# User_Interface.net
KiCad netlist of a schematic drawn in Altium Designer
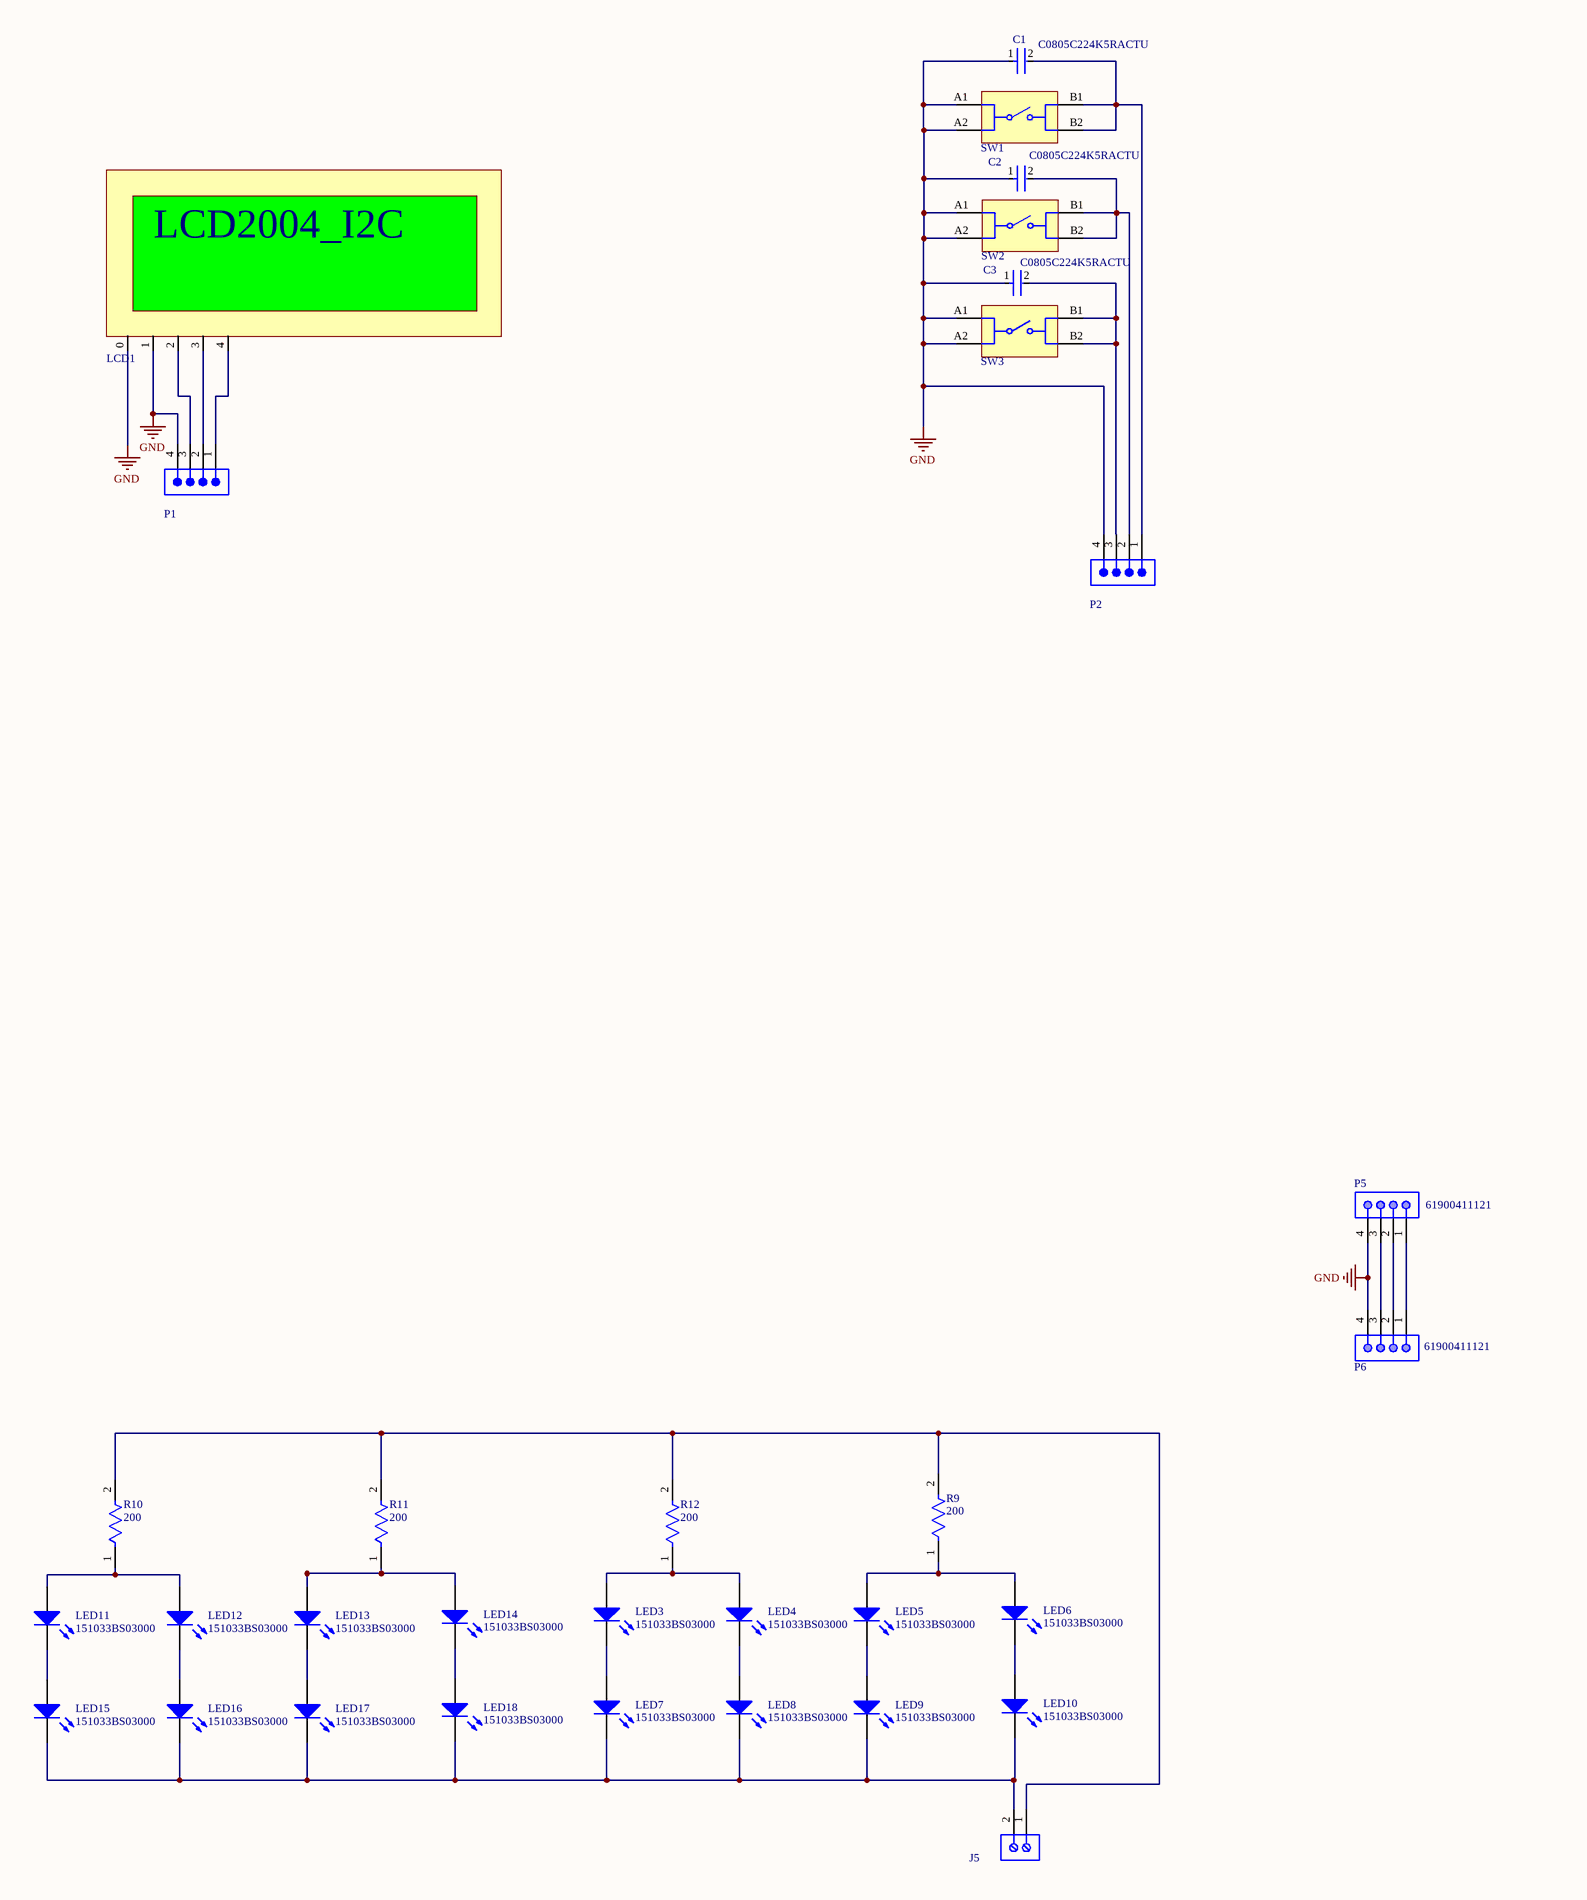
[diagram p0: User_Interface.SchDoc, left]
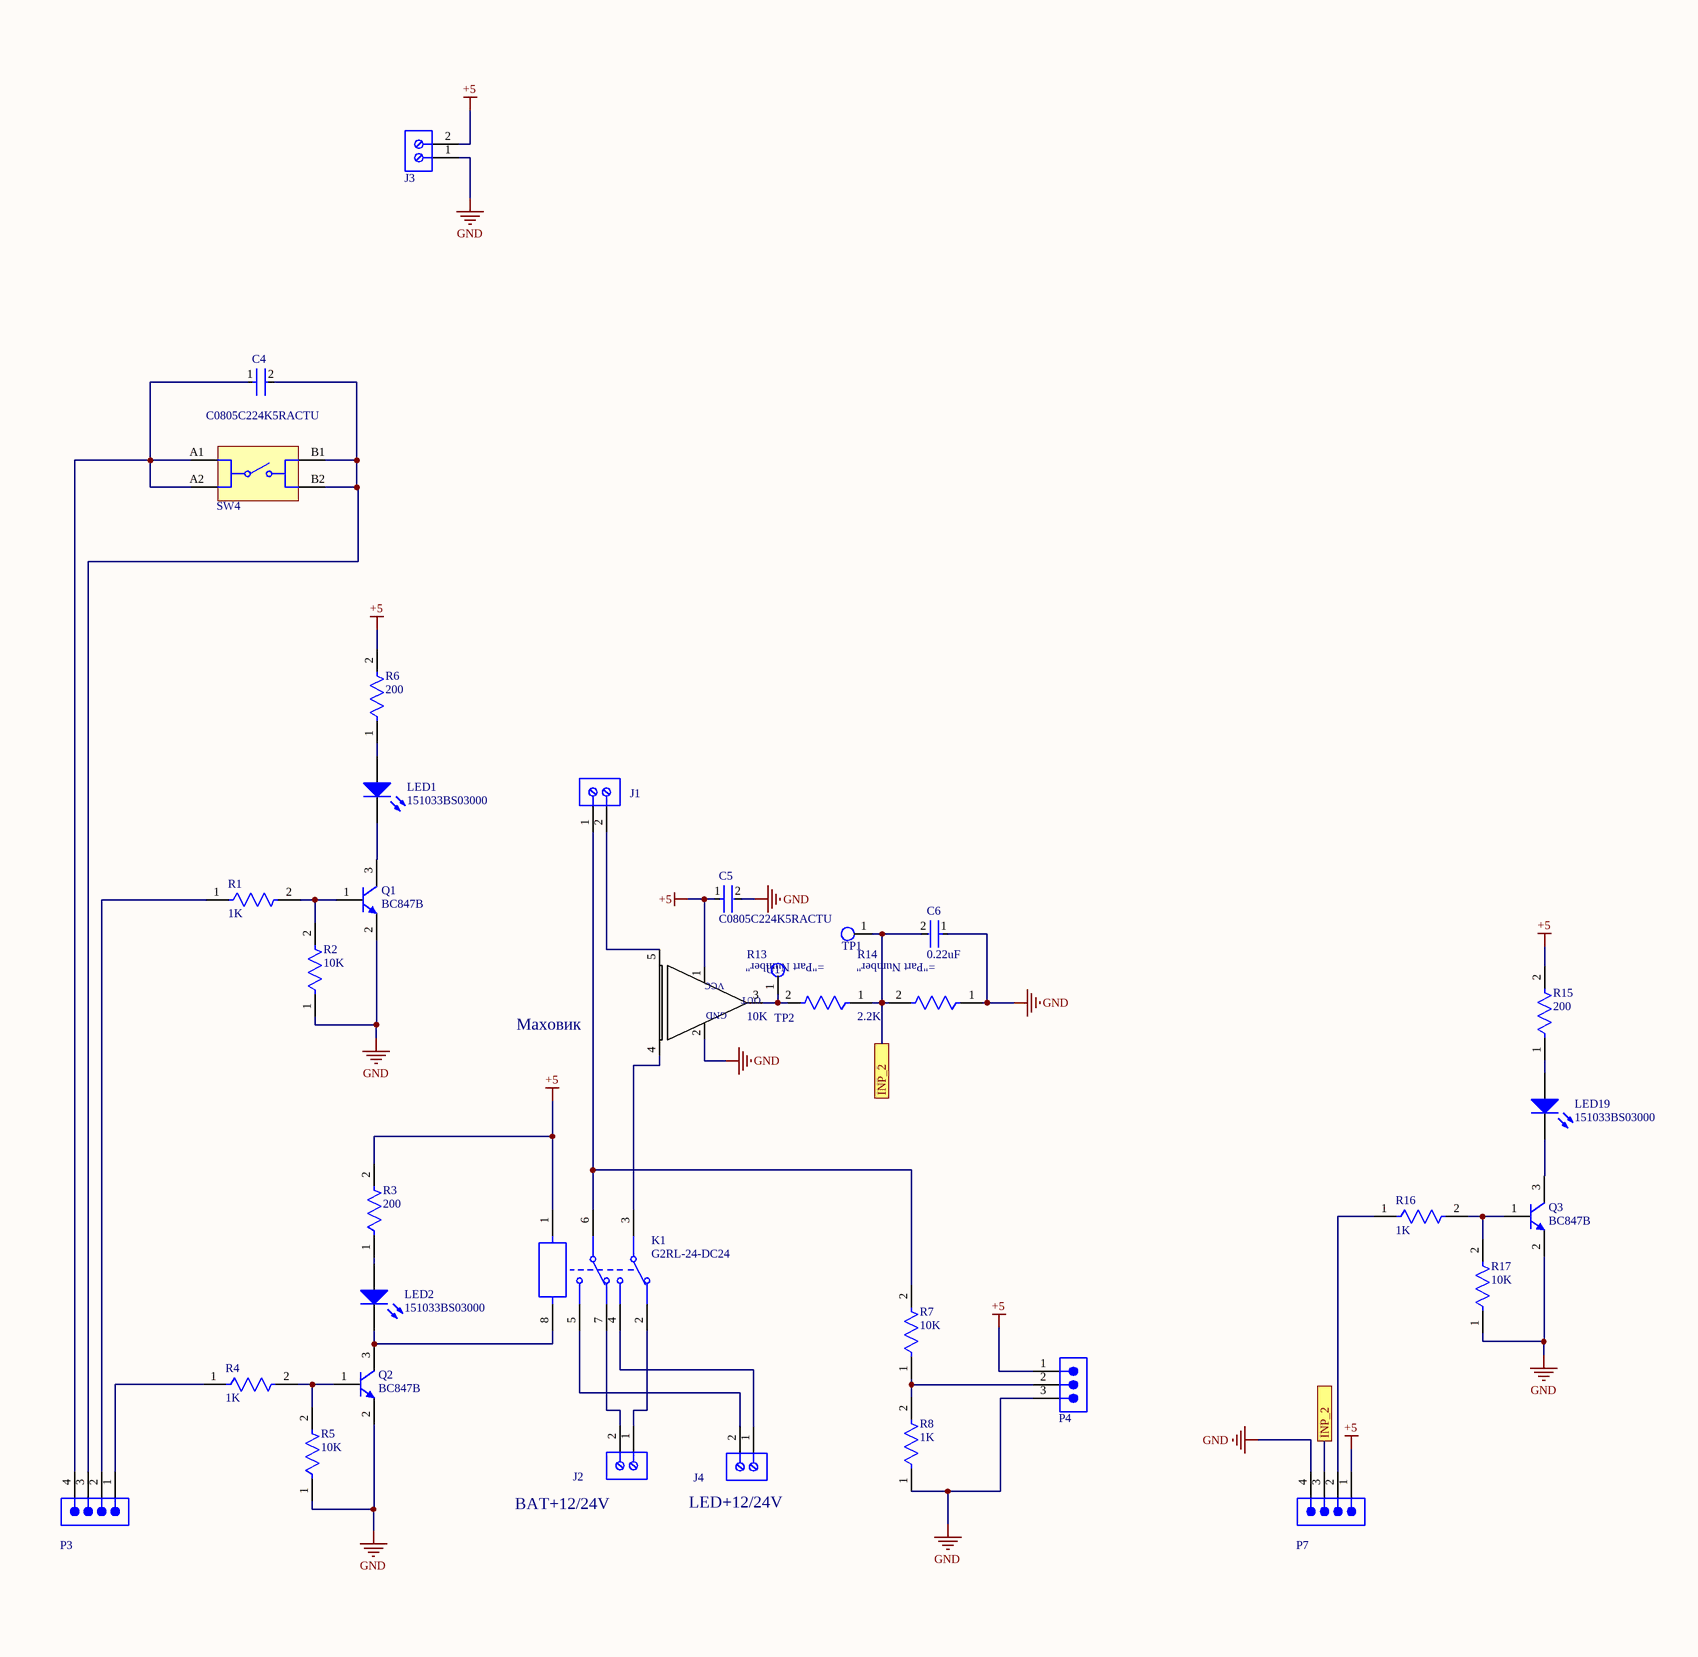
[diagram p1: User_Interface.SchDoc, right]

(export (version "E")
  (design (tool "Eeschema 10.0.6"))
  (components
    (comp (ref "C1")
      (value "C0805C224K5RACTU")
      (footprint "FP-C0805C-DN-IPC_A")
      (description "CAP CER 0.22UF 50V X7R 0805")
      (fields
        (field (name "MANUFACTURER") "KEMET")
        (field (name "OCTOPART") "https://octopart.com/c0805c224k5ractu-kemet-144670")
      )
      (libsource (lib "Pasive_components") (part "CMP-1036-04552-2"))
    )
    (comp (ref "C2")
      (value "C0805C224K5RACTU")
      (footprint "FP-C0805C-DN-IPC_A")
      (description "CAP CER 0.22UF 50V X7R 0805")
      (fields
        (field (name "MANUFACTURER") "KEMET")
        (field (name "OCTOPART") "https://octopart.com/c0805c224k5ractu-kemet-144670")
      )
      (libsource (lib "Pasive_components") (part "CMP-1036-04552-2"))
    )
    (comp (ref "C3")
      (value "C0805C224K5RACTU")
      (footprint "FP-C0805C-DN-IPC_A")
      (description "CAP CER 0.22UF 50V X7R 0805")
      (fields
        (field (name "MANUFACTURER") "KEMET")
        (field (name "OCTOPART") "https://octopart.com/c0805c224k5ractu-kemet-144670")
      )
      (libsource (lib "Pasive_components") (part "CMP-1036-04552-2"))
    )
    (comp (ref "C4")
      (value "C0805C224K5RACTU")
      (footprint "FP-C0805C-DN-IPC_A")
      (description "CAP CER 0.22UF 50V X7R 0805")
      (fields
        (field (name "MANUFACTURER") "KEMET")
        (field (name "OCTOPART") "https://octopart.com/c0805c224k5ractu-kemet-144670")
      )
      (libsource (lib "Pasive_components") (part "CMP-1036-04552-2"))
    )
    (comp (ref "C5")
      (value "C0805C224K5RACTU")
      (footprint "FP-C0805C-DN-MFG")
      (description "CAP CER 0.22UF 50V X7R 0805")
      (fields
        (field (name "MANUFACTURER") "KEMET")
        (field (name "OCTOPART") "https://octopart.com/c0805c224k5ractu-kemet-144670")
      )
      (libsource (lib "Altium Content Vault") (part "b4654b650e69147ec39a6b967a45e02"))
    )
    (comp (ref "C6")
      (value "0.22uF")
      (footprint "FP-C0805C-DN-MFG")
      (description "CAP CER 0.22UF 50V X7R 0805")
      (fields
        (field (name "MANUFACTURER") "KEMET")
        (field (name "OCTOPART") "https://octopart.com/c0805c224k5ractu-kemet-144670")
      )
      (libsource (lib "Altium Content Vault") (part "b4654b650e69147ec39a6b967a45e02"))
    )
    (comp (ref "J1")
      (value "691101710002")
      (footprint "691101710002")
      (description "WR-TBL Series 101 Horizontal Entry Modular, THT, pitch 5mm, 2p")
      (fields (field (name "MANUFACTURER") "Wurth Elektronik"))
      (libsource (lib "Altium_WR-TBL (rev23a)") (part "691101710002"))
    )
    (comp (ref "J2")
      (value "691101710002")
      (footprint "691101710002")
      (description "WR-TBL Series 101 Horizontal Entry Modular, THT, pitch 5mm, 2p")
      (fields (field (name "MANUFACTURER") "Wurth Elektronik"))
      (libsource (lib "Altium_WR-TBL (rev23a)") (part "691101710002"))
    )
    (comp (ref "J3")
      (value "691101710002")
      (footprint "691101710002")
      (description "WR-TBL Series 101 Horizontal Entry Modular, THT, pitch 5mm, 2p")
      (fields (field (name "MANUFACTURER") "Wurth Elektronik"))
      (libsource (lib "Altium_WR-TBL (rev23a)") (part "691101710002"))
    )
    (comp (ref "J4")
      (value "691101710002")
      (footprint "691101710002")
      (description "WR-TBL Series 101 Horizontal Entry Modular, THT, pitch 5mm, 2p")
      (fields (field (name "MANUFACTURER") "Wurth Elektronik"))
      (libsource (lib "Altium_WR-TBL (rev23a)") (part "691101710002"))
    )
    (comp (ref "J5")
      (value "691101710002")
      (footprint "691101710002")
      (description "WR-TBL Series 101 Horizontal Entry Modular, THT, pitch 5mm, 2p")
      (fields (field (name "MANUFACTURER") "Wurth Elektronik"))
      (libsource (lib "Altium_WR-TBL (rev23a)") (part "691101710002"))
    )
    (comp (ref "K1")
      (value "G2RL-24-DC24")
      (footprint "OMRON-G2RL-24_V")
      (fields (field (name "MANUFACTURER") "Omron"))
      (libsource (lib "Altium Content Vault") (part "RELAY-DPDT-8_C"))
    )
    (comp (ref "LCD1")
      (value "2004_I2C")
      (footprint "LCD2004_I2C")
      (libsource (lib "LCD2004_I2C") (part "LCD2004_I2C"))
    )
    (comp (ref "LED1")
      (value "151033BS03000")
      (footprint "Type 3mm")
      (description "THT LED round mono-color waterclear, WL-TMRW , Blue")
      (fields (field (name "MANUFACTURER") "Wuerth Elektronik"))
      (libsource (lib "Optic-LED") (part "151033BS03000"))
    )
    (comp (ref "LED2")
      (value "151033BS03000")
      (footprint "Type 3mm")
      (description "THT LED round mono-color waterclear, WL-TMRW , Blue")
      (fields (field (name "MANUFACTURER") "Wuerth Elektronik"))
      (libsource (lib "Optic-LED") (part "151033BS03000"))
    )
    (comp (ref "LED3")
      (value "151033BS03000")
      (footprint "Type 3mm")
      (description "THT LED round mono-color waterclear, WL-TMRW , Blue")
      (fields (field (name "MANUFACTURER") "Wuerth Elektronik"))
      (libsource (lib "Optic-LED") (part "151033BS03000"))
    )
    (comp (ref "LED4")
      (value "151033BS03000")
      (footprint "Type 3mm")
      (description "THT LED round mono-color waterclear, WL-TMRW , Blue")
      (fields (field (name "MANUFACTURER") "Wuerth Elektronik"))
      (libsource (lib "Optic-LED") (part "151033BS03000"))
    )
    (comp (ref "LED5")
      (value "151033BS03000")
      (footprint "Type 3mm")
      (description "THT LED round mono-color waterclear, WL-TMRW , Blue")
      (fields (field (name "MANUFACTURER") "Wuerth Elektronik"))
      (libsource (lib "Optic-LED") (part "151033BS03000"))
    )
    (comp (ref "LED6")
      (value "151033BS03000")
      (footprint "Type 3mm")
      (description "THT LED round mono-color waterclear, WL-TMRW , Blue")
      (fields (field (name "MANUFACTURER") "Wuerth Elektronik"))
      (libsource (lib "Optic-LED") (part "151033BS03000"))
    )
    (comp (ref "LED7")
      (value "151033BS03000")
      (footprint "Type 3mm")
      (description "THT LED round mono-color waterclear, WL-TMRW , Blue")
      (fields (field (name "MANUFACTURER") "Wuerth Elektronik"))
      (libsource (lib "Optic-LED") (part "151033BS03000"))
    )
    (comp (ref "LED8")
      (value "151033BS03000")
      (footprint "Type 3mm")
      (description "THT LED round mono-color waterclear, WL-TMRW , Blue")
      (fields (field (name "MANUFACTURER") "Wuerth Elektronik"))
      (libsource (lib "Optic-LED") (part "151033BS03000"))
    )
    (comp (ref "LED9")
      (value "151033BS03000")
      (footprint "Type 3mm")
      (description "THT LED round mono-color waterclear, WL-TMRW , Blue")
      (fields (field (name "MANUFACTURER") "Wuerth Elektronik"))
      (libsource (lib "Optic-LED") (part "151033BS03000"))
    )
    (comp (ref "LED10")
      (value "151033BS03000")
      (footprint "Type 3mm")
      (description "THT LED round mono-color waterclear, WL-TMRW , Blue")
      (fields (field (name "MANUFACTURER") "Wuerth Elektronik"))
      (libsource (lib "Optic-LED") (part "151033BS03000"))
    )
    (comp (ref "LED11")
      (value "151033BS03000")
      (footprint "Type 3mm")
      (description "THT LED round mono-color waterclear, WL-TMRW , Blue")
      (fields (field (name "MANUFACTURER") "Wuerth Elektronik"))
      (libsource (lib "Optic-LED") (part "151033BS03000"))
    )
    (comp (ref "LED12")
      (value "151033BS03000")
      (footprint "Type 3mm")
      (description "THT LED round mono-color waterclear, WL-TMRW , Blue")
      (fields (field (name "MANUFACTURER") "Wuerth Elektronik"))
      (libsource (lib "Optic-LED") (part "151033BS03000"))
    )
    (comp (ref "LED13")
      (value "151033BS03000")
      (footprint "Type 3mm")
      (description "THT LED round mono-color waterclear, WL-TMRW , Blue")
      (fields (field (name "MANUFACTURER") "Wuerth Elektronik"))
      (libsource (lib "Optic-LED") (part "151033BS03000"))
    )
    (comp (ref "LED14")
      (value "151033BS03000")
      (footprint "Type 3mm")
      (description "THT LED round mono-color waterclear, WL-TMRW , Blue")
      (fields (field (name "MANUFACTURER") "Wuerth Elektronik"))
      (libsource (lib "Optic-LED") (part "151033BS03000"))
    )
    (comp (ref "LED15")
      (value "151033BS03000")
      (footprint "Type 3mm")
      (description "THT LED round mono-color waterclear, WL-TMRW , Blue")
      (fields (field (name "MANUFACTURER") "Wuerth Elektronik"))
      (libsource (lib "Optic-LED") (part "151033BS03000"))
    )
    (comp (ref "LED16")
      (value "151033BS03000")
      (footprint "Type 3mm")
      (description "THT LED round mono-color waterclear, WL-TMRW , Blue")
      (fields (field (name "MANUFACTURER") "Wuerth Elektronik"))
      (libsource (lib "Optic-LED") (part "151033BS03000"))
    )
    (comp (ref "LED17")
      (value "151033BS03000")
      (footprint "Type 3mm")
      (description "THT LED round mono-color waterclear, WL-TMRW , Blue")
      (fields (field (name "MANUFACTURER") "Wuerth Elektronik"))
      (libsource (lib "Optic-LED") (part "151033BS03000"))
    )
    (comp (ref "LED18")
      (value "151033BS03000")
      (footprint "Type 3mm")
      (description "THT LED round mono-color waterclear, WL-TMRW , Blue")
      (fields (field (name "MANUFACTURER") "Wuerth Elektronik"))
      (libsource (lib "Optic-LED") (part "151033BS03000"))
    )
    (comp (ref "LED19")
      (value "151033BS03000")
      (footprint "Type 3mm")
      (description "THT LED round mono-color waterclear, WL-TMRW , Blue")
      (fields (field (name "MANUFACTURER") "Wuerth Elektronik"))
      (libsource (lib "Optic-LED") (part "151033BS03000"))
    )
    (comp (ref "P1")
      (value "61900411121")
      (footprint "61900411121")
      (description "WR-WTB THT Male Vertical Locking Header, pitch 2.54mm, 4pins")
      (fields (field (name "MANUFACTURER") "Wurth Elektronik"))
      (libsource (lib "Altium_WR-WTB (rev22b)") (part "61900411121"))
    )
    (comp (ref "P2")
      (value "61900411121")
      (footprint "61900411121")
      (description "WR-WTB THT Male Vertical Locking Header, pitch 2.54mm, 4pins")
      (fields (field (name "MANUFACTURER") "Wurth Elektronik"))
      (libsource (lib "Altium_WR-WTB (rev22b)") (part "61900411121"))
    )
    (comp (ref "P3")
      (value "61900411121")
      (footprint "61900411121")
      (description "WR-WTB THT Male Vertical Locking Header, pitch 2.54mm, 4pins")
      (fields (field (name "MANUFACTURER") "Wurth Elektronik"))
      (libsource (lib "Altium_WR-WTB (rev22b)") (part "61900411121"))
    )
    (comp (ref "P4")
      (value "61900311121")
      (footprint "61900311121")
      (description "WR-WTB THT Male Vertical Locking Header, pitch 2.54mm, 3pins")
      (fields (field (name "MANUFACTURER") "Wurth Elektronik"))
      (libsource (lib "Altium_WR-WTB (rev22b)") (part "61900311121"))
    )
    (comp (ref "P5")
      (value "61900411121")
      (footprint "61900411121")
      (description "WR-WTB THT Male Vertical Locking Header, pitch 2.54mm, 4p")
      (fields (field (name "PUBLISHER") "Wurth Elektronik"))
      (libsource (lib "Altium_WR-WTB (rev20a)") (part "61900411121"))
    )
    (comp (ref "P6")
      (value "61900411121")
      (footprint "61900411121")
      (description "WR-WTB THT Male Vertical Locking Header, pitch 2.54mm, 4p")
      (fields (field (name "PUBLISHER") "Wurth Elektronik"))
      (libsource (lib "Altium_WR-WTB (rev20a)") (part "61900411121"))
    )
    (comp (ref "P7")
      (value "61900411121")
      (footprint "61900411121")
      (description "WR-WTB THT Male Vertical Locking Header, pitch 2.54mm, 4pins")
      (fields (field (name "MANUFACTURER") "Wurth Elektronik"))
      (libsource (lib "Altium_WR-WTB (rev22b)") (part "61900411121"))
    )
    (comp (ref "Q1")
      (value "BC847B")
      (footprint "INF-SOT23_M")
      (description "NPN Silicon AF Transistor, 45 V VCEO, 100 mA IC, SOT23, Reel, Green")
      (fields (field (name "MANUFACTURER") "Infineon"))
      (libsource (lib "Altium Content Vault") (part "INF-BJTNPN-BEC-3"))
    )
    (comp (ref "Q2")
      (value "BC847B")
      (footprint "INF-SOT23_M")
      (description "NPN Silicon AF Transistor, 45 V VCEO, 100 mA IC, SOT23, Reel, Green")
      (fields (field (name "MANUFACTURER") "Infineon"))
      (libsource (lib "Altium Content Vault") (part "INF-BJTNPN-BEC-3"))
    )
    (comp (ref "Q3")
      (value "BC847B")
      (footprint "INF-SOT23_M")
      (description "NPN Silicon AF Transistor, 45 V VCEO, 100 mA IC, SOT23, Reel, Green")
      (fields (field (name "MANUFACTURER") "Infineon"))
      (libsource (lib "Altium Content Vault") (part "INF-BJTNPN-BEC-3"))
    )
    (comp (ref "R1")
      (value "1K")
      (footprint "FP-CRCW0805-e3-MFG")
      (description "RES Thick Film, 10kΩ, 1%, 0.125W, 100ppm/°C, 0805")
      (fields (field (name "TOLERANCE") "1%"))
      (libsource (lib "Pasive_components") (part "CMP-2001-04908-2"))
    )
    (comp (ref "R2")
      (value "10K")
      (footprint "FP-CRCW0805-e3-MFG")
      (description "RES Thick Film, 10kΩ, 1%, 0.125W, 100ppm/°C, 0805")
      (fields (field (name "TOLERANCE") "1%"))
      (libsource (lib "Pasive_components") (part "CMP-2001-04908-2"))
    )
    (comp (ref "R3")
      (value "200")
      (footprint "FP-CRCW0805-e3-MFG")
      (description "RES Thick Film, 200Ω, 1%, 0.125W, 100ppm/°C, 0805")
      (fields (field (name "TOLERANCE") "1%"))
      (libsource (lib "Pasive_components") (part "CMP-2001-04908-2"))
    )
    (comp (ref "R4")
      (value "1K")
      (footprint "FP-CRCW0805-e3-MFG")
      (description "RES Thick Film, 1kΩ, 1%, 0.125W, 100ppm/°C, 0805")
      (fields (field (name "TOLERANCE") "1%"))
      (libsource (lib "Pasive_components") (part "CMP-2001-04908-2"))
    )
    (comp (ref "R5")
      (value "10K")
      (footprint "FP-CRCW0805-e3-MFG")
      (description "RES Thick Film, 10kΩ, 1%, 0.125W, 100ppm/°C, 0805")
      (fields (field (name "TOLERANCE") "1%"))
      (libsource (lib "Pasive_components") (part "CMP-2001-04908-2"))
    )
    (comp (ref "R6")
      (value "200")
      (footprint "FP-CRCW0805-e3-MFG")
      (description "RES Thick Film, 200Ω, 1%, 0.125W, 100ppm/°C, 0805")
      (fields (field (name "TOLERANCE") "1%"))
      (libsource (lib "Pasive_components") (part "CMP-2001-04908-2"))
    )
    (comp (ref "R7")
      (value "10K")
      (footprint "FP-CRCW0805-e3-MFG")
      (description "RES Thick Film, 10kΩ, 1%, 0.125W, 100ppm/°C, 0805")
      (fields (field (name "TOLERANCE") "1%"))
      (libsource (lib "Pasive_components") (part "CMP-2001-04908-2"))
    )
    (comp (ref "R8")
      (value "1K")
      (footprint "FP-CRCW0805-e3-MFG")
      (description "RES Thick Film, 1kΩ, 1%, 0.125W, 100ppm/°C, 0805")
      (fields (field (name "TOLERANCE") "1%"))
      (libsource (lib "Pasive_components") (part "CMP-2001-04908-2"))
    )
    (comp (ref "R9")
      (value "200")
      (footprint "FP-CRCW0805-e3-MFG")
      (description "RES Thick Film, 200Ω, 1%, 0.125W, 100ppm/°C, 0805")
      (fields (field (name "TOLERANCE") "1%"))
      (libsource (lib "Pasive_components") (part "CMP-2001-04908-2"))
    )
    (comp (ref "R10")
      (value "200")
      (footprint "FP-CRCW0805-e3-MFG")
      (description "RES Thick Film, 200Ω, 1%, 0.125W, 100ppm/°C, 0805")
      (fields (field (name "TOLERANCE") "1%"))
      (libsource (lib "Pasive_components") (part "CMP-2001-04908-2"))
    )
    (comp (ref "R11")
      (value "200")
      (footprint "FP-CRCW0805-e3-MFG")
      (description "RES Thick Film, 200Ω, 1%, 0.125W, 100ppm/°C, 0805")
      (fields (field (name "TOLERANCE") "1%"))
      (libsource (lib "Pasive_components") (part "CMP-2001-04908-2"))
    )
    (comp (ref "R12")
      (value "200")
      (footprint "FP-CRCW0805-e3-MFG")
      (description "RES Thick Film, 200Ω, 1%, 0.125W, 100ppm/°C, 0805")
      (fields (field (name "TOLERANCE") "1%"))
      (libsource (lib "Pasive_components") (part "CMP-2001-04908-2"))
    )
    (comp (ref "R13")
      (value "10K")
      (footprint "Vishay_CRCW0805-e3_IPC_A")
      (libsource (lib "Res_Yageo_RC0805FR-07100KL_eec") (part "RC0805FR-07100KL"))
    )
    (comp (ref "R14")
      (value "2.2K")
      (footprint "Vishay_CRCW0805-e3_IPC_A")
      (libsource (lib "Res_Yageo_RC0805FR-07100KL_eec") (part "RC0805FR-07100KL"))
    )
    (comp (ref "R15")
      (value "200")
      (footprint "FP-CRCW0805-e3-MFG")
      (description "RES Thick Film, 200Ω, 1%, 0.125W, 100ppm/°C, 0805")
      (fields (field (name "TOLERANCE") "1%"))
      (libsource (lib "Pasive_components") (part "CMP-2001-04908-2"))
    )
    (comp (ref "R16")
      (value "1K")
      (footprint "FP-CRCW0805-e3-MFG")
      (description "RES Thick Film, 10kΩ, 1%, 0.125W, 100ppm/°C, 0805")
      (fields (field (name "TOLERANCE") "1%"))
      (libsource (lib "Pasive_components") (part "CMP-2001-04908-2"))
    )
    (comp (ref "R17")
      (value "10K")
      (footprint "FP-CRCW0805-e3-MFG")
      (description "RES Thick Film, 10kΩ, 1%, 0.125W, 100ppm/°C, 0805")
      (fields (field (name "TOLERANCE") "1%"))
      (libsource (lib "Pasive_components") (part "CMP-2001-04908-2"))
    )
    (comp (ref "SW1")
      (value "430156043726")
      (footprint "4301x60437x6")
      (description "WS-TATV THT Tact Switch 6x6mm, SPST-NO, 12VDC, 50mA, 260g")
      (fields (field (name "MANUFACTURER") "Wurth Elektronik"))
      (libsource (lib "Altium_WS-TATV (rev22a)") (part "430156043726"))
    )
    (comp (ref "SW2")
      (value "430156043726")
      (footprint "4301x60437x6")
      (description "WS-TATV THT Tact Switch 6x6mm, SPST-NO, 12VDC, 50mA, 260g")
      (fields (field (name "MANUFACTURER") "Wurth Elektronik"))
      (libsource (lib "Altium_WS-TATV (rev22a)") (part "430156043726"))
    )
    (comp (ref "SW3")
      (value "430156043726")
      (footprint "4301x60437x6")
      (description "WS-TATV THT Tact Switch 6x6mm, SPST-NO, 12VDC, 50mA, 260g")
      (fields (field (name "MANUFACTURER") "Wurth Elektronik"))
      (libsource (lib "Altium_WS-TATV (rev22a)") (part "430156043726"))
    )
    (comp (ref "SW4")
      (value "430156043726")
      (footprint "4301x60437x6")
      (description "WS-TATV THT Tact Switch 6x6mm, SPST-NO, 12VDC, 50mA, 260g")
      (fields (field (name "MANUFACTURER") "Wurth Elektronik"))
      (libsource (lib "Altium_WS-TATV (rev22a)") (part "430156043726"))
    )
    (comp (ref "TP1")
      (value "Test_Point_PCB")
      (footprint "Test_Point")
      (description "Test_Point")
      (libsource (lib "Test_Point") (part "TP_PCB?"))
    )
    (comp (ref "TP2")
      (value "Test_Point_PCB")
      (footprint "Test_Point")
      (description "Test_Point")
      (libsource (lib "Test_Point") (part "TP_PCB?"))
    )
    (comp (ref "U1") (value "ACS758") (footprint "ACS758-100") (libsource (lib "ACS758") (part "ACS758")))
  )
  (nets
    (net (code "1") (name "+5") (class "Default")
      (node (ref "C5") (pin "1") (pinfunction "1_1") (pintype "passive"))
      (node (ref "J3") (pin "2") (pinfunction "2_2") (pintype "passive"))
      (node (ref "K1") (pin "1") (pinfunction "1_1") (pintype "passive"))
      (node (ref "P4") (pin "1") (pinfunction "1_1") (pintype "passive"))
      (node (ref "P7") (pin "1") (pinfunction "1_1") (pintype "passive"))
      (node (ref "R15") (pin "2") (pinfunction "2_2") (pintype "passive"))
      (node (ref "R3") (pin "2") (pinfunction "2_2") (pintype "passive"))
      (node (ref "R6") (pin "2") (pinfunction "2_2") (pintype "passive"))
      (node (ref "U1") (pin "1") (pinfunction "+VCC_1") (pintype "passive"))
    )
    (net (code "2") (name "/INP_2") (class "Default")
      (node (ref "C6") (pin "2") (pinfunction "2_2") (pintype "passive"))
      (node (ref "P7") (pin "3") (pinfunction "3_3") (pintype "passive"))
      (node (ref "R13") (pin "1") (pinfunction "1_1") (pintype "passive"))
      (node (ref "R14") (pin "2") (pinfunction "2_2") (pintype "passive"))
      (node (ref "TP1") (pin "1") (pinfunction "G9_1") (pintype "passive"))
    )
    (net (code "3") (name "GND") (class "Default")
      (node (ref "C1") (pin "1") (pinfunction "1_1") (pintype "passive"))
      (node (ref "C2") (pin "1") (pinfunction "1_1") (pintype "passive"))
      (node (ref "C3") (pin "1") (pinfunction "1_1") (pintype "passive"))
      (node (ref "C5") (pin "2") (pinfunction "2_2") (pintype "passive"))
      (node (ref "C6") (pin "1") (pinfunction "1_1") (pintype "passive"))
      (node (ref "J3") (pin "1") (pinfunction "1_1") (pintype "passive"))
      (node (ref "LCD1") (pin "0") (pinfunction "0_0") (pintype "passive"))
      (node (ref "LCD1") (pin "1") (pinfunction "1_1") (pintype "passive"))
      (node (ref "P1") (pin "4") (pinfunction "4_4") (pintype "passive"))
      (node (ref "P2") (pin "4") (pinfunction "4_4") (pintype "passive"))
      (node (ref "P4") (pin "3") (pinfunction "3_3") (pintype "passive"))
      (node (ref "P5") (pin "4") (pinfunction "4_4") (pintype "passive"))
      (node (ref "P6") (pin "4") (pinfunction "4_4") (pintype "passive"))
      (node (ref "P7") (pin "4") (pinfunction "4_4") (pintype "passive"))
      (node (ref "Q1") (pin "2") (pinfunction "E_2") (pintype "passive"))
      (node (ref "Q2") (pin "2") (pinfunction "E_2") (pintype "passive"))
      (node (ref "Q3") (pin "2") (pinfunction "E_2") (pintype "passive"))
      (node (ref "R14") (pin "1") (pinfunction "1_1") (pintype "passive"))
      (node (ref "R17") (pin "1") (pinfunction "1_1") (pintype "passive"))
      (node (ref "R2") (pin "1") (pinfunction "1_1") (pintype "passive"))
      (node (ref "R5") (pin "1") (pinfunction "1_1") (pintype "passive"))
      (node (ref "R8") (pin "1") (pinfunction "1_1") (pintype "passive"))
      (node (ref "SW1") (pin "A1") (pinfunction "A1_A1") (pintype "passive"))
      (node (ref "SW1") (pin "A2") (pinfunction "A2_A2") (pintype "passive"))
      (node (ref "SW2") (pin "A1") (pinfunction "A1_A1") (pintype "passive"))
      (node (ref "SW2") (pin "A2") (pinfunction "A2_A2") (pintype "passive"))
      (node (ref "SW3") (pin "A1") (pinfunction "A1_A1") (pintype "passive"))
      (node (ref "SW3") (pin "A2") (pinfunction "A2_A2") (pintype "passive"))
      (node (ref "U1") (pin "2") (pinfunction "GND_2") (pintype "passive"))
    )
    (net (code "4") (name "Net-(C1-Pad2)") (class "Default")
      (node (ref "C1") (pin "2") (pinfunction "2_2") (pintype "passive"))
      (node (ref "P2") (pin "1") (pinfunction "1_1") (pintype "passive"))
      (node (ref "SW1") (pin "B1") (pinfunction "B1_B1") (pintype "passive"))
      (node (ref "SW1") (pin "B2") (pinfunction "B2_B2") (pintype "passive"))
    )
    (net (code "5") (name "Net-(C2-Pad2)") (class "Default")
      (node (ref "C2") (pin "2") (pinfunction "2_2") (pintype "passive"))
      (node (ref "P2") (pin "2") (pinfunction "2_2") (pintype "passive"))
      (node (ref "SW2") (pin "B1") (pinfunction "B1_B1") (pintype "passive"))
      (node (ref "SW2") (pin "B2") (pinfunction "B2_B2") (pintype "passive"))
    )
    (net (code "6") (name "Net-(C3-Pad2)") (class "Default")
      (node (ref "C3") (pin "2") (pinfunction "2_2") (pintype "passive"))
      (node (ref "P2") (pin "3") (pinfunction "3_3") (pintype "passive"))
      (node (ref "SW3") (pin "B1") (pinfunction "B1_B1") (pintype "passive"))
      (node (ref "SW3") (pin "B2") (pinfunction "B2_B2") (pintype "passive"))
    )
    (net (code "7") (name "Net-(C4-Pad1)") (class "Default")
      (node (ref "C4") (pin "1") (pinfunction "1_1") (pintype "passive"))
      (node (ref "P3") (pin "4") (pinfunction "4_4") (pintype "passive"))
      (node (ref "SW4") (pin "A1") (pinfunction "A1_A1") (pintype "passive"))
      (node (ref "SW4") (pin "A2") (pinfunction "A2_A2") (pintype "passive"))
    )
    (net (code "8") (name "Net-(C4-Pad2)") (class "Default")
      (node (ref "C4") (pin "2") (pinfunction "2_2") (pintype "passive"))
      (node (ref "P3") (pin "3") (pinfunction "3_3") (pintype "passive"))
      (node (ref "SW4") (pin "B1") (pinfunction "B1_B1") (pintype "passive"))
      (node (ref "SW4") (pin "B2") (pinfunction "B2_B2") (pintype "passive"))
    )
    (net (code "9") (name "Net-(J1-Pad1)") (class "Default")
      (node (ref "J1") (pin "1") (pinfunction "1_1") (pintype "passive"))
      (node (ref "K1") (pin "6") (pinfunction "6_6") (pintype "passive"))
      (node (ref "R7") (pin "2") (pinfunction "2_2") (pintype "passive"))
    )
    (net (code "10") (name "Net-(J2-Pad1)") (class "Default")
      (node (ref "J2") (pin "1") (pinfunction "1_1") (pintype "passive"))
      (node (ref "K1") (pin "2") (pinfunction "2_2") (pintype "passive"))
    )
    (net (code "11") (name "Net-(J2-Pad2)") (class "Default")
      (node (ref "J2") (pin "2") (pinfunction "2_2") (pintype "passive"))
      (node (ref "K1") (pin "7") (pinfunction "7_7") (pintype "passive"))
    )
    (net (code "12") (name "Net-(J4-Pad1)") (class "Default")
      (node (ref "J4") (pin "1") (pinfunction "1_1") (pintype "passive"))
      (node (ref "K1") (pin "4") (pinfunction "4_4") (pintype "passive"))
    )
    (net (code "13") (name "Net-(J4-Pad2)") (class "Default")
      (node (ref "J4") (pin "2") (pinfunction "2_2") (pintype "passive"))
      (node (ref "K1") (pin "5") (pinfunction "5_5") (pintype "passive"))
    )
    (net (code "14") (name "Net-(J5-Pad1)") (class "Default")
      (node (ref "J5") (pin "1") (pinfunction "1_1") (pintype "passive"))
      (node (ref "R10") (pin "2") (pinfunction "2_2") (pintype "passive"))
      (node (ref "R11") (pin "2") (pinfunction "2_2") (pintype "passive"))
      (node (ref "R12") (pin "2") (pinfunction "2_2") (pintype "passive"))
      (node (ref "R9") (pin "2") (pinfunction "2_2") (pintype "passive"))
    )
    (net (code "15") (name "Net-(LCD1-Pad2)") (class "Default")
      (node (ref "LCD1") (pin "2") (pinfunction "2_2") (pintype "passive"))
      (node (ref "P1") (pin "3") (pinfunction "3_3") (pintype "passive"))
    )
    (net (code "16") (name "Net-(LCD1-Pad3)") (class "Default")
      (node (ref "LCD1") (pin "3") (pinfunction "3_3") (pintype "passive"))
      (node (ref "P1") (pin "2") (pinfunction "2_2") (pintype "passive"))
    )
    (net (code "17") (name "Net-(LCD1-Pad4)") (class "Default")
      (node (ref "LCD1") (pin "4") (pinfunction "4_4") (pintype "passive"))
      (node (ref "P1") (pin "1") (pinfunction "1_1") (pintype "passive"))
    )
    (net (code "18") (name "Net-(LED1-A)") (class "Default")
      (node (ref "LED1") (pin "2") (pinfunction "A_2") (pintype "passive"))
      (node (ref "R6") (pin "1") (pinfunction "1_1") (pintype "passive"))
    )
    (net (code "19") (name "Net-(LED1-K)") (class "Default")
      (node (ref "LED1") (pin "1") (pinfunction "K_1") (pintype "passive"))
      (node (ref "Q1") (pin "3") (pinfunction "C_3") (pintype "passive"))
    )
    (net (code "20") (name "Net-(LED2-A)") (class "Default")
      (node (ref "LED2") (pin "2") (pinfunction "A_2") (pintype "passive"))
      (node (ref "R3") (pin "1") (pinfunction "1_1") (pintype "passive"))
    )
    (net (code "21") (name "Net-(LED2-K)") (class "Default")
      (node (ref "K1") (pin "8") (pinfunction "8_8") (pintype "passive"))
      (node (ref "LED2") (pin "1") (pinfunction "K_1") (pintype "passive"))
      (node (ref "Q2") (pin "3") (pinfunction "C_3") (pintype "passive"))
    )
    (net (code "22") (name "Net-(LED3-A)") (class "Default")
      (node (ref "LED3") (pin "2") (pinfunction "A_2") (pintype "passive"))
      (node (ref "LED4") (pin "2") (pinfunction "A_2") (pintype "passive"))
      (node (ref "R12") (pin "1") (pinfunction "1_1") (pintype "passive"))
    )
    (net (code "23") (name "Net-(LED3-K)") (class "Default")
      (node (ref "LED3") (pin "1") (pinfunction "K_1") (pintype "passive"))
      (node (ref "LED7") (pin "2") (pinfunction "A_2") (pintype "passive"))
    )
    (net (code "24") (name "Net-(LED4-K)") (class "Default")
      (node (ref "LED4") (pin "1") (pinfunction "K_1") (pintype "passive"))
      (node (ref "LED8") (pin "2") (pinfunction "A_2") (pintype "passive"))
    )
    (net (code "25") (name "Net-(LED5-A)") (class "Default")
      (node (ref "LED5") (pin "2") (pinfunction "A_2") (pintype "passive"))
      (node (ref "LED6") (pin "2") (pinfunction "A_2") (pintype "passive"))
      (node (ref "R9") (pin "1") (pinfunction "1_1") (pintype "passive"))
    )
    (net (code "26") (name "Net-(LED5-K)") (class "Default")
      (node (ref "LED5") (pin "1") (pinfunction "K_1") (pintype "passive"))
      (node (ref "LED9") (pin "2") (pinfunction "A_2") (pintype "passive"))
    )
    (net (code "27") (name "Net-(LED10-A)") (class "Default")
      (node (ref "LED10") (pin "2") (pinfunction "A_2") (pintype "passive"))
      (node (ref "LED6") (pin "1") (pinfunction "K_1") (pintype "passive"))
    )
    (net (code "28") (name "Net-(LED10-K)") (class "Default")
      (node (ref "J5") (pin "2") (pinfunction "2_2") (pintype "passive"))
      (node (ref "LED10") (pin "1") (pinfunction "K_1") (pintype "passive"))
      (node (ref "LED15") (pin "1") (pinfunction "K_1") (pintype "passive"))
      (node (ref "LED16") (pin "1") (pinfunction "K_1") (pintype "passive"))
      (node (ref "LED17") (pin "1") (pinfunction "K_1") (pintype "passive"))
      (node (ref "LED18") (pin "1") (pinfunction "K_1") (pintype "passive"))
      (node (ref "LED7") (pin "1") (pinfunction "K_1") (pintype "passive"))
      (node (ref "LED8") (pin "1") (pinfunction "K_1") (pintype "passive"))
      (node (ref "LED9") (pin "1") (pinfunction "K_1") (pintype "passive"))
    )
    (net (code "29") (name "Net-(LED11-A)") (class "Default")
      (node (ref "LED11") (pin "2") (pinfunction "A_2") (pintype "passive"))
      (node (ref "LED12") (pin "2") (pinfunction "A_2") (pintype "passive"))
      (node (ref "R10") (pin "1") (pinfunction "1_1") (pintype "passive"))
    )
    (net (code "30") (name "Net-(LED11-K)") (class "Default")
      (node (ref "LED11") (pin "1") (pinfunction "K_1") (pintype "passive"))
      (node (ref "LED15") (pin "2") (pinfunction "A_2") (pintype "passive"))
    )
    (net (code "31") (name "Net-(LED12-K)") (class "Default")
      (node (ref "LED12") (pin "1") (pinfunction "K_1") (pintype "passive"))
      (node (ref "LED16") (pin "2") (pinfunction "A_2") (pintype "passive"))
    )
    (net (code "32") (name "Net-(LED13-A)") (class "Default")
      (node (ref "LED13") (pin "2") (pinfunction "A_2") (pintype "passive"))
      (node (ref "LED14") (pin "2") (pinfunction "A_2") (pintype "passive"))
      (node (ref "R11") (pin "1") (pinfunction "1_1") (pintype "passive"))
    )
    (net (code "33") (name "Net-(LED13-K)") (class "Default")
      (node (ref "LED13") (pin "1") (pinfunction "K_1") (pintype "passive"))
      (node (ref "LED17") (pin "2") (pinfunction "A_2") (pintype "passive"))
    )
    (net (code "34") (name "Net-(LED14-K)") (class "Default")
      (node (ref "LED14") (pin "1") (pinfunction "K_1") (pintype "passive"))
      (node (ref "LED18") (pin "2") (pinfunction "A_2") (pintype "passive"))
    )
    (net (code "35") (name "Net-(LED19-A)") (class "Default")
      (node (ref "LED19") (pin "2") (pinfunction "A_2") (pintype "passive"))
      (node (ref "R15") (pin "1") (pinfunction "1_1") (pintype "passive"))
    )
    (net (code "36") (name "Net-(LED19-K)") (class "Default")
      (node (ref "LED19") (pin "1") (pinfunction "K_1") (pintype "passive"))
      (node (ref "Q3") (pin "3") (pinfunction "C_3") (pintype "passive"))
    )
    (net (code "37") (name "Net-(P3-Pad1)") (class "Default")
      (node (ref "P3") (pin "1") (pinfunction "1_1") (pintype "passive"))
      (node (ref "R4") (pin "1") (pinfunction "1_1") (pintype "passive"))
    )
    (net (code "38") (name "Net-(P3-Pad2)") (class "Default")
      (node (ref "P3") (pin "2") (pinfunction "2_2") (pintype "passive"))
      (node (ref "R1") (pin "1") (pinfunction "1_1") (pintype "passive"))
    )
    (net (code "39") (name "Net-(P4-Pad2)") (class "Default")
      (node (ref "P4") (pin "2") (pinfunction "2_2") (pintype "passive"))
      (node (ref "R7") (pin "1") (pinfunction "1_1") (pintype "passive"))
      (node (ref "R8") (pin "2") (pinfunction "2_2") (pintype "passive"))
    )
    (net (code "40") (name "Net-(P5-Pad1)") (class "Default")
      (node (ref "P5") (pin "1") (pinfunction "1_1") (pintype "passive"))
      (node (ref "P6") (pin "1") (pinfunction "1_1") (pintype "passive"))
    )
    (net (code "41") (name "Net-(P5-Pad2)") (class "Default")
      (node (ref "P5") (pin "2") (pinfunction "2_2") (pintype "passive"))
      (node (ref "P6") (pin "2") (pinfunction "2_2") (pintype "passive"))
    )
    (net (code "42") (name "Net-(P5-Pad3)") (class "Default")
      (node (ref "P5") (pin "3") (pinfunction "3_3") (pintype "passive"))
      (node (ref "P6") (pin "3") (pinfunction "3_3") (pintype "passive"))
    )
    (net (code "43") (name "Net-(P7-Pad2)") (class "Default")
      (node (ref "P7") (pin "2") (pinfunction "2_2") (pintype "passive"))
      (node (ref "R16") (pin "1") (pinfunction "1_1") (pintype "passive"))
    )
    (net (code "44") (name "Net-(Q1-B)") (class "Default")
      (node (ref "Q1") (pin "1") (pinfunction "B_1") (pintype "passive"))
      (node (ref "R1") (pin "2") (pinfunction "2_2") (pintype "passive"))
      (node (ref "R2") (pin "2") (pinfunction "2_2") (pintype "passive"))
    )
    (net (code "45") (name "Net-(Q2-B)") (class "Default")
      (node (ref "Q2") (pin "1") (pinfunction "B_1") (pintype "passive"))
      (node (ref "R4") (pin "2") (pinfunction "2_2") (pintype "passive"))
      (node (ref "R5") (pin "2") (pinfunction "2_2") (pintype "passive"))
    )
    (net (code "46") (name "Net-(Q3-B)") (class "Default")
      (node (ref "Q3") (pin "1") (pinfunction "B_1") (pintype "passive"))
      (node (ref "R16") (pin "2") (pinfunction "2_2") (pintype "passive"))
      (node (ref "R17") (pin "2") (pinfunction "2_2") (pintype "passive"))
    )
    (net (code "47") (name "Net-(TP2-G9)") (class "Default")
      (node (ref "R13") (pin "2") (pinfunction "2_2") (pintype "passive"))
      (node (ref "TP2") (pin "1") (pinfunction "G9_1") (pintype "passive"))
      (node (ref "U1") (pin "3") (pinfunction "OUT_3") (pintype "passive"))
    )
    (net (code "48") (name "Net-(U1-+IP)") (class "Default")
      (node (ref "K1") (pin "3") (pinfunction "3_3") (pintype "passive"))
      (node (ref "U1") (pin "4") (pinfunction "+IP_4") (pintype "passive"))
    )
    (net (code "49") (name "Net-(U1--IP)") (class "Default")
      (node (ref "J1") (pin "2") (pinfunction "2_2") (pintype "passive"))
      (node (ref "U1") (pin "5") (pinfunction "-IP_5") (pintype "passive"))
    )
  )
)
